# TMP112_Breakout.net
KiCad netlist of a schematic drawn in EAGLE
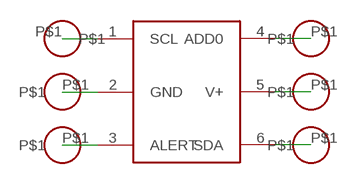
[diagram p0: schematic, sheet 1]

(export (version "E")
  (design (tool "Eeschema 10.0.6"))
  (components
    (comp (ref "U$1")
      (value "TMP112")
      (footprint "eagle-import:TMP112")
      (libsource (lib "eagle-import") (part "TMP112"))
    )
    (comp (ref "U$2")
      (value "VIA")
      (footprint "eagle-import:VIA")
      (libsource (lib "eagle-import") (part "VIA"))
    )
    (comp (ref "U$3")
      (value "VIA")
      (footprint "eagle-import:VIA")
      (libsource (lib "eagle-import") (part "VIA"))
    )
    (comp (ref "U$4")
      (value "VIA")
      (footprint "eagle-import:VIA")
      (libsource (lib "eagle-import") (part "VIA"))
    )
    (comp (ref "U$5")
      (value "VIA")
      (footprint "eagle-import:VIA")
      (libsource (lib "eagle-import") (part "VIA"))
    )
    (comp (ref "U$6")
      (value "VIA")
      (footprint "eagle-import:VIA")
      (libsource (lib "eagle-import") (part "VIA"))
    )
    (comp (ref "U$7")
      (value "VIA")
      (footprint "eagle-import:VIA")
      (libsource (lib "eagle-import") (part "VIA"))
    )
  )
  (nets
    (net (code "1") (name "Net-(U$1-ADD0)") (class "Default")
      (node (ref "U$1") (pin "4") (pinfunction "ADD0_4") (pintype "bidirectional"))
      (node (ref "U$7") (pin "P$1") (pinfunction "P$1_P$1") (pintype "bidirectional"))
    )
    (net (code "2") (name "Net-(U$1-ALERT)") (class "Default")
      (node (ref "U$1") (pin "3") (pinfunction "ALERT_3") (pintype "bidirectional"))
      (node (ref "U$4") (pin "P$1") (pinfunction "P$1_P$1") (pintype "bidirectional"))
    )
    (net (code "3") (name "Net-(U$1-GND)") (class "Default")
      (node (ref "U$1") (pin "2") (pinfunction "GND_2") (pintype "bidirectional"))
      (node (ref "U$3") (pin "P$1") (pinfunction "P$1_P$1") (pintype "bidirectional"))
    )
    (net (code "4") (name "Net-(U$1-SCL)") (class "Default")
      (node (ref "U$1") (pin "1") (pinfunction "SCL_1") (pintype "bidirectional"))
      (node (ref "U$2") (pin "P$1") (pinfunction "P$1_P$1") (pintype "bidirectional"))
    )
    (net (code "5") (name "Net-(U$1-SDA)") (class "Default")
      (node (ref "U$1") (pin "6") (pinfunction "SDA_6") (pintype "bidirectional"))
      (node (ref "U$5") (pin "P$1") (pinfunction "P$1_P$1") (pintype "bidirectional"))
    )
    (net (code "6") (name "Net-(U$1-V+)") (class "Default")
      (node (ref "U$1") (pin "5") (pinfunction "V+_5") (pintype "bidirectional"))
      (node (ref "U$6") (pin "P$1") (pinfunction "P$1_P$1") (pintype "bidirectional"))
    )
  )
)
